# GeekIMUv1_Reciver.net
KiCad netlist of a schematic drawn in Altium Designer
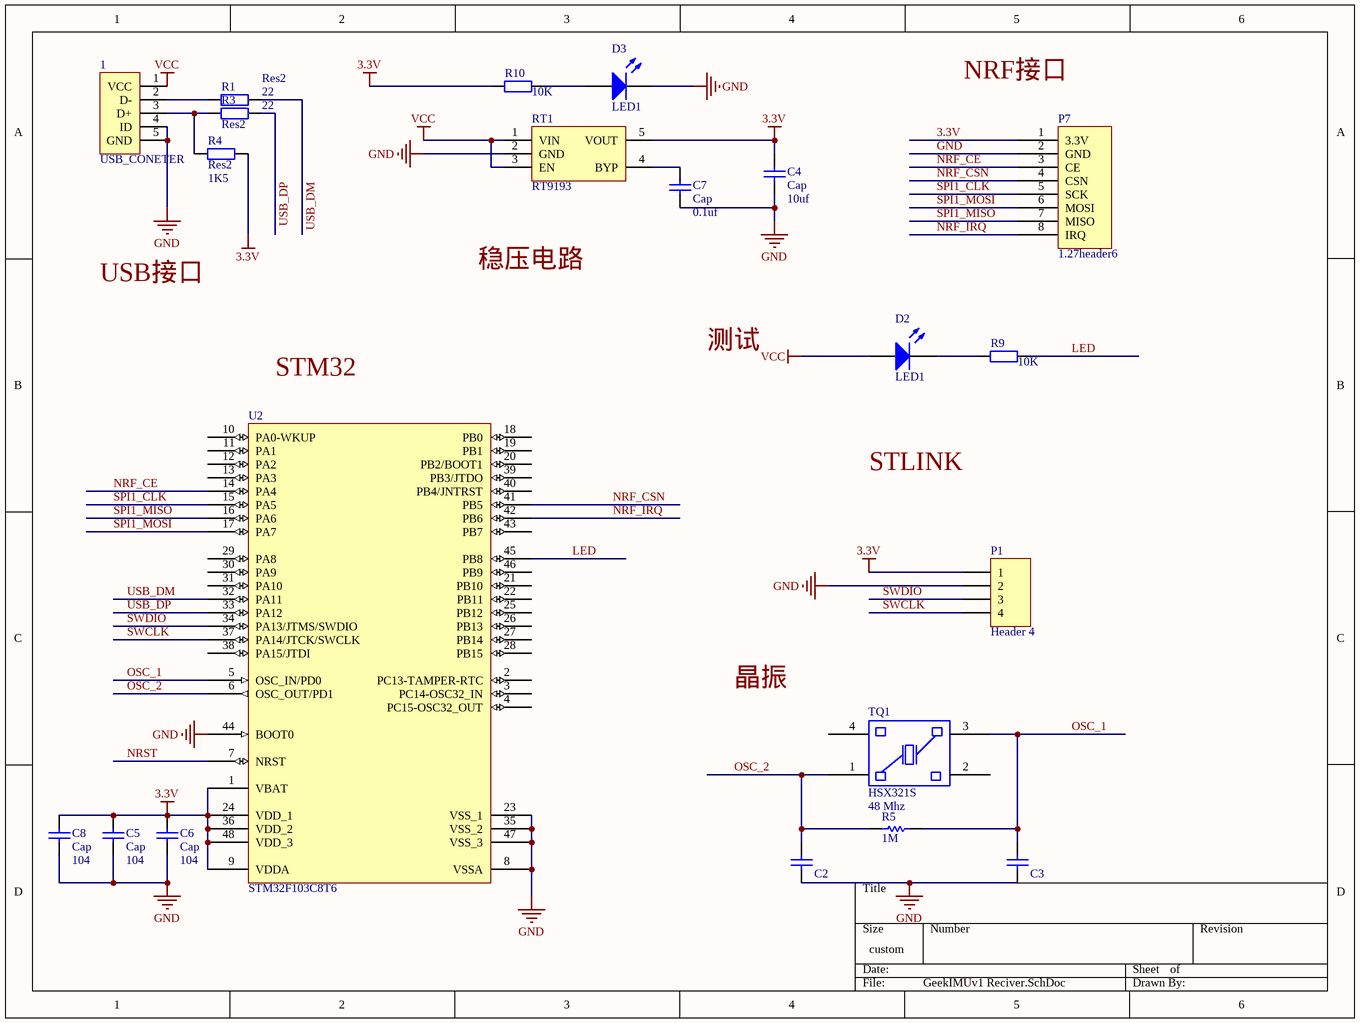
[diagram p0: GeekIMUv1 Reciver.SchDoc]

(export (version "E")
  (design (tool "Eeschema 10.0.6"))
  (components
    (comp (ref "1")
      (value "USB_CONETER")
      (footprint "USB A Plug")
      (description "USB")
      (fields (field (name "PUBLISHER") "Altium Limited"))
      (libsource (lib "my1012") (part "USB_conect_B"))
    )
    (comp (ref "C2") (value "Cap") (footprint "C0402") (libsource (lib "refLib") (part "Cap")))
    (comp (ref "C3") (value "Cap") (footprint "C0402") (libsource (lib "refLib") (part "Cap")))
    (comp (ref "C4")
      (value "Cap")
      (footprint "C0603")
      (description "Capacitor")
      (fields (field (name "ALTIUM_VALUE") "10uf") (field (name "PUBLISHER") "Altium Limited"))
      (libsource (lib "Miscellaneous Devices") (part "Cap"))
    )
    (comp (ref "C5")
      (value "Cap")
      (footprint "C0402")
      (description "Capacitor")
      (fields (field (name "ALTIUM_VALUE") "104") (field (name "PUBLISHER") "Altium Limited"))
      (libsource (lib "my1012") (part "Cap"))
    )
    (comp (ref "C6")
      (value "Cap")
      (footprint "C0402")
      (description "Capacitor")
      (fields (field (name "ALTIUM_VALUE") "104") (field (name "PUBLISHER") "Altium Limited"))
      (libsource (lib "my1012") (part "Cap"))
    )
    (comp (ref "C7")
      (value "Cap")
      (footprint "B0402")
      (description "Capacitor")
      (fields (field (name "ALTIUM_VALUE") "0.1uf") (field (name "PUBLISHER") "Altium Limited"))
      (libsource (lib "Miscellaneous Devices") (part "Cap"))
    )
    (comp (ref "C8")
      (value "Cap")
      (footprint "C0402")
      (description "Capacitor")
      (fields (field (name "ALTIUM_VALUE") "104") (field (name "PUBLISHER") "Altium Limited"))
      (libsource (lib "my1012") (part "Cap"))
    )
    (comp (ref "D2")
      (value "LED1")
      (footprint "C0402")
      (description "Typical RED GaAs LED")
      (fields (field (name "PUBLISHER") "Altium Limited"))
      (libsource (lib "my1012") (part "LED1"))
    )
    (comp (ref "D3")
      (value "LED1")
      (footprint "C0402")
      (description "Typical RED GaAs LED")
      (fields (field (name "PUBLISHER") "Altium Limited"))
      (libsource (lib "my1012") (part "LED1"))
    )
    (comp (ref "P1")
      (value "Header 4")
      (footprint "HDR1X4")
      (description "Header, 4-Pin")
      (fields (field (name "PUBLISHER") "Altium Limited"))
      (libsource (lib "Miscellaneous Connectors") (part "Header 4"))
    )
    (comp (ref "P7")
      (value "1.27header6")
      (footprint "1.27header6")
      (libsource (lib "1.27header6") (part "1.27header6"))
    )
    (comp (ref "R1")
      (value "Res2")
      (footprint "B0402")
      (description "Resistor")
      (fields (field (name "ALTIUM_VALUE") "22") (field (name "PUBLISHER") "Altium Limited"))
      (libsource (lib "my1012") (part "Res2"))
    )
    (comp (ref "R3")
      (value "Res2")
      (footprint "B0402")
      (description "Resistor")
      (fields (field (name "ALTIUM_VALUE") "22") (field (name "PUBLISHER") "Altium Limited"))
      (libsource (lib "my1012") (part "Res2"))
    )
    (comp (ref "R4")
      (value "Res2")
      (footprint "B0402")
      (description "Resistor")
      (fields (field (name "ALTIUM_VALUE") "1K5") (field (name "PUBLISHER") "Altium Limited"))
      (libsource (lib "my1012") (part "Res2"))
    )
    (comp (ref "R5")
      (value "1M")
      (footprint "R0402")
      (description "Semiconductor Resistor")
      (fields (field (name "Comment") "Res Semi"))
      (libsource (lib "refLib") (part "Res Semi"))
    )
    (comp (ref "R9")
      (value "10K")
      (footprint "B0402")
      (description "Resistor")
      (fields (field (name "PUBLISHER") "Altium Limited"))
      (libsource (lib "") (part "Res2_1"))
    )
    (comp (ref "R10")
      (value "10K")
      (footprint "B0402")
      (description "Resistor")
      (fields (field (name "PUBLISHER") "Altium Limited"))
      (libsource (lib "") (part "Res2_1"))
    )
    (comp (ref "RT1")
      (value "RT9193")
      (footprint "SOT23-5")
      (description "Power")
      (libsource (lib "SmartIMU") (part "RT9193"))
    )
    (comp (ref "TQ1")
      (value "HSX321S")
      (footprint "DSX321G")
      (description "XTAL")
      (fields (field (name "ALTIUM_VALUE") "48 Mhz"))
      (libsource (lib "refLib") (part "HSX321S"))
    )
    (comp (ref "U2")
      (value "STM32F103C8T6")
      (footprint "LQFP48")
      (description "STM32 ARM-based 32-bit MCU with 64 Kbytes Flash, 48-pin LQFP, Industrial Temperature")
      (fields (field (name "PUBLISHER") "Altium Limited"))
      (libsource (lib "ST Microcontroller 32-Bit STM32") (part "STM32F103C8T6"))
    )
  )
  (nets
    (net (code "1") (name "/LED") (class "Default")
      (node (ref "R9") (pin "1") (pinfunction "1_1") (pintype "passive"))
      (node (ref "U2") (pin "45") (pinfunction "PB8_45") (pintype "bidirectional"))
    )
    (net (code "2") (name "/NRF_CE") (class "Default")
      (node (ref "P7") (pin "3") (pinfunction "CE_3") (pintype "passive"))
      (node (ref "U2") (pin "14") (pinfunction "PA4_14") (pintype "bidirectional"))
    )
    (net (code "3") (name "/NRF_CSN") (class "Default")
      (node (ref "P7") (pin "4") (pinfunction "CSN_4") (pintype "passive"))
      (node (ref "U2") (pin "41") (pinfunction "PB5_41") (pintype "bidirectional"))
    )
    (net (code "4") (name "/NRF_IRQ") (class "Default")
      (node (ref "P7") (pin "8") (pinfunction "IRQ_8") (pintype "passive"))
      (node (ref "U2") (pin "42") (pinfunction "PB6_42") (pintype "bidirectional"))
    )
    (net (code "6") (name "/NRST") (class "Default")
      (node (ref "U2") (pin "7") (pinfunction "NRST_7") (pintype "bidirectional"))
    )
    (net (code "7") (name "/OSC_1") (class "Default")
      (node (ref "C3") (pin "2") (pinfunction "2_2") (pintype "passive"))
      (node (ref "R5") (pin "2") (pinfunction "2_2") (pintype "passive"))
      (node (ref "TQ1") (pin "3") (pinfunction "3_3") (pintype "passive"))
      (node (ref "U2") (pin "5") (pinfunction "OSC_IN/PD0_5") (pintype "input"))
    )
    (net (code "8") (name "/OSC_2") (class "Default")
      (node (ref "C2") (pin "2") (pinfunction "2_2") (pintype "passive"))
      (node (ref "R5") (pin "1") (pinfunction "1_1") (pintype "passive"))
      (node (ref "TQ1") (pin "1") (pinfunction "1_1") (pintype "passive"))
      (node (ref "U2") (pin "6") (pinfunction "OSC_OUT/PD1_6") (pintype "output"))
    )
    (net (code "9") (name "/SPI1_CLK") (class "Default")
      (node (ref "P7") (pin "5") (pinfunction "SCK_5") (pintype "passive"))
      (node (ref "U2") (pin "15") (pinfunction "PA5_15") (pintype "bidirectional"))
    )
    (net (code "10") (name "/SPI1_MISO") (class "Default")
      (node (ref "P7") (pin "7") (pinfunction "MISO_7") (pintype "passive"))
      (node (ref "U2") (pin "16") (pinfunction "PA6_16") (pintype "bidirectional"))
    )
    (net (code "11") (name "/SPI1_MOSI") (class "Default")
      (node (ref "P7") (pin "6") (pinfunction "MOSI_6") (pintype "passive"))
      (node (ref "U2") (pin "17") (pinfunction "PA7_17") (pintype "bidirectional"))
    )
    (net (code "14") (name "/SWCLK") (class "Default")
      (node (ref "P1") (pin "4") (pinfunction "4_4") (pintype "passive"))
      (node (ref "U2") (pin "37") (pinfunction "PA14/JTCK/SWCLK_37") (pintype "bidirectional"))
    )
    (net (code "15") (name "/SWDIO") (class "Default")
      (node (ref "P1") (pin "3") (pinfunction "3_3") (pintype "passive"))
      (node (ref "U2") (pin "34") (pinfunction "PA13/JTMS/SWDIO_34") (pintype "bidirectional"))
    )
    (net (code "16") (name "/USB_DM") (class "Default")
      (node (ref "R1") (pin "2") (pinfunction "2_2") (pintype "passive"))
      (node (ref "U2") (pin "32") (pinfunction "PA11_32") (pintype "bidirectional"))
    )
    (net (code "17") (name "/USB_DP") (class "Default")
      (node (ref "R3") (pin "2") (pinfunction "2_2") (pintype "passive"))
      (node (ref "U2") (pin "33") (pinfunction "PA12_33") (pintype "bidirectional"))
    )
    (net (code "22") (name "3.3V") (class "Default")
      (node (ref "C4") (pin "2") (pinfunction "2_2") (pintype "passive"))
      (node (ref "C5") (pin "2") (pinfunction "2_2") (pintype "passive"))
      (node (ref "C6") (pin "2") (pinfunction "2_2") (pintype "passive"))
      (node (ref "C8") (pin "2") (pinfunction "2_2") (pintype "passive"))
      (node (ref "P1") (pin "1") (pinfunction "1_1") (pintype "passive"))
      (node (ref "P7") (pin "1") (pinfunction "3.3V_1") (pintype "passive"))
      (node (ref "R10") (pin "2") (pinfunction "2_2") (pintype "passive"))
      (node (ref "R4") (pin "2") (pinfunction "2_2") (pintype "passive"))
      (node (ref "RT1") (pin "5") (pinfunction "VOUT_5") (pintype "passive"))
      (node (ref "U2") (pin "1") (pinfunction "VBAT_1") (pintype "power_in"))
      (node (ref "U2") (pin "24") (pinfunction "VDD_1_24") (pintype "power_in"))
      (node (ref "U2") (pin "36") (pinfunction "VDD_2_36") (pintype "power_in"))
      (node (ref "U2") (pin "48") (pinfunction "VDD_3_48") (pintype "power_in"))
      (node (ref "U2") (pin "9") (pinfunction "VDDA_9") (pintype "power_in"))
    )
    (net (code "23") (name "GND") (class "Default")
      (node (ref "1") (pin "4") (pinfunction "ID_4") (pintype "passive"))
      (node (ref "1") (pin "5") (pinfunction "GND_5") (pintype "passive"))
      (node (ref "C2") (pin "1") (pinfunction "1_1") (pintype "passive"))
      (node (ref "C3") (pin "1") (pinfunction "1_1") (pintype "passive"))
      (node (ref "C4") (pin "1") (pinfunction "1_1") (pintype "passive"))
      (node (ref "C5") (pin "1") (pinfunction "1_1") (pintype "passive"))
      (node (ref "C6") (pin "1") (pinfunction "1_1") (pintype "passive"))
      (node (ref "C7") (pin "1") (pinfunction "1_1") (pintype "passive"))
      (node (ref "C8") (pin "1") (pinfunction "1_1") (pintype "passive"))
      (node (ref "D3") (pin "2") (pinfunction "K_2") (pintype "passive"))
      (node (ref "P1") (pin "2") (pinfunction "2_2") (pintype "passive"))
      (node (ref "P7") (pin "2") (pinfunction "GND_2") (pintype "passive"))
      (node (ref "RT1") (pin "2") (pinfunction "GND_2") (pintype "passive"))
      (node (ref "U2") (pin "23") (pinfunction "VSS_1_23") (pintype "power_in"))
      (node (ref "U2") (pin "35") (pinfunction "VSS_2_35") (pintype "power_in"))
      (node (ref "U2") (pin "44") (pinfunction "BOOT0_44") (pintype "input"))
      (node (ref "U2") (pin "47") (pinfunction "VSS_3_47") (pintype "power_in"))
      (node (ref "U2") (pin "8") (pinfunction "VSSA_8") (pintype "power_in"))
    )
    (net (code "24") (name "Net-(1-D+)") (class "Default")
      (node (ref "1") (pin "3") (pinfunction "D+_3") (pintype "passive"))
      (node (ref "R3") (pin "1") (pinfunction "1_1") (pintype "passive"))
      (node (ref "R4") (pin "1") (pinfunction "1_1") (pintype "passive"))
    )
    (net (code "25") (name "Net-(1-D-)") (class "Default")
      (node (ref "1") (pin "2") (pinfunction "D-_2") (pintype "passive"))
      (node (ref "R1") (pin "1") (pinfunction "1_1") (pintype "passive"))
    )
    (net (code "26") (name "Net-(D2-K)") (class "Default")
      (node (ref "D2") (pin "2") (pinfunction "K_2") (pintype "passive"))
      (node (ref "R9") (pin "2") (pinfunction "2_2") (pintype "passive"))
    )
    (net (code "27") (name "Net-(D3-A)") (class "Default")
      (node (ref "D3") (pin "1") (pinfunction "A_1") (pintype "passive"))
      (node (ref "R10") (pin "1") (pinfunction "1_1") (pintype "passive"))
    )
    (net (code "28") (name "Net-(RT1-BYP)") (class "Default")
      (node (ref "C7") (pin "2") (pinfunction "2_2") (pintype "passive"))
      (node (ref "RT1") (pin "4") (pinfunction "BYP_4") (pintype "passive"))
    )
    (net (code "29") (name "VCC") (class "Default")
      (node (ref "1") (pin "1") (pinfunction "VCC_1") (pintype "passive"))
      (node (ref "D2") (pin "1") (pinfunction "A_1") (pintype "passive"))
      (node (ref "RT1") (pin "1") (pinfunction "VIN_1") (pintype "passive"))
      (node (ref "RT1") (pin "3") (pinfunction "EN_3") (pintype "power_in"))
    )
    (net (code "30") (name "unconnected-(TQ1-Pad2)") (class "Default")
      (node (ref "TQ1") (pin "2") (pinfunction "2_2") (pintype "passive"))
    )
    (net (code "31") (name "unconnected-(TQ1-Pad4)") (class "Default")
      (node (ref "TQ1") (pin "4") (pinfunction "4_4") (pintype "passive"))
    )
    (net (code "32") (name "unconnected-(U2-PA0-WKUP-Pad10)") (class "Default")
      (node (ref "U2") (pin "10") (pinfunction "PA0-WKUP_10") (pintype "bidirectional"))
    )
    (net (code "33") (name "unconnected-(U2-PA1-Pad11)") (class "Default")
      (node (ref "U2") (pin "11") (pinfunction "PA1_11") (pintype "bidirectional"))
    )
    (net (code "34") (name "unconnected-(U2-PA2-Pad12)") (class "Default")
      (node (ref "U2") (pin "12") (pinfunction "PA2_12") (pintype "bidirectional"))
    )
    (net (code "35") (name "unconnected-(U2-PA3-Pad13)") (class "Default")
      (node (ref "U2") (pin "13") (pinfunction "PA3_13") (pintype "bidirectional"))
    )
    (net (code "36") (name "unconnected-(U2-PA8-Pad29)") (class "Default")
      (node (ref "U2") (pin "29") (pinfunction "PA8_29") (pintype "bidirectional"))
    )
    (net (code "37") (name "unconnected-(U2-PA9-Pad30)") (class "Default")
      (node (ref "U2") (pin "30") (pinfunction "PA9_30") (pintype "bidirectional"))
    )
    (net (code "38") (name "unconnected-(U2-PA10-Pad31)") (class "Default")
      (node (ref "U2") (pin "31") (pinfunction "PA10_31") (pintype "bidirectional"))
    )
    (net (code "39") (name "unconnected-(U2-PA15{slash}JTDI-Pad38)") (class "Default")
      (node (ref "U2") (pin "38") (pinfunction "PA15/JTDI_38") (pintype "bidirectional"))
    )
    (net (code "40") (name "unconnected-(U2-PB0-Pad18)") (class "Default")
      (node (ref "U2") (pin "18") (pinfunction "PB0_18") (pintype "bidirectional"))
    )
    (net (code "41") (name "unconnected-(U2-PB1-Pad19)") (class "Default")
      (node (ref "U2") (pin "19") (pinfunction "PB1_19") (pintype "bidirectional"))
    )
    (net (code "42") (name "unconnected-(U2-PB2{slash}BOOT1-Pad20)") (class "Default")
      (node (ref "U2") (pin "20") (pinfunction "PB2/BOOT1_20") (pintype "bidirectional"))
    )
    (net (code "43") (name "unconnected-(U2-PB3{slash}JTDO-Pad39)") (class "Default")
      (node (ref "U2") (pin "39") (pinfunction "PB3/JTDO_39") (pintype "bidirectional"))
    )
    (net (code "44") (name "unconnected-(U2-PB4{slash}JNTRST-Pad40)") (class "Default")
      (node (ref "U2") (pin "40") (pinfunction "PB4/JNTRST_40") (pintype "bidirectional"))
    )
    (net (code "45") (name "unconnected-(U2-PB7-Pad43)") (class "Default")
      (node (ref "U2") (pin "43") (pinfunction "PB7_43") (pintype "bidirectional"))
    )
    (net (code "46") (name "unconnected-(U2-PB9-Pad46)") (class "Default")
      (node (ref "U2") (pin "46") (pinfunction "PB9_46") (pintype "bidirectional"))
    )
    (net (code "47") (name "unconnected-(U2-PB10-Pad21)") (class "Default")
      (node (ref "U2") (pin "21") (pinfunction "PB10_21") (pintype "bidirectional"))
    )
    (net (code "48") (name "unconnected-(U2-PB11-Pad22)") (class "Default")
      (node (ref "U2") (pin "22") (pinfunction "PB11_22") (pintype "bidirectional"))
    )
    (net (code "49") (name "unconnected-(U2-PB12-Pad25)") (class "Default")
      (node (ref "U2") (pin "25") (pinfunction "PB12_25") (pintype "bidirectional"))
    )
    (net (code "50") (name "unconnected-(U2-PB13-Pad26)") (class "Default")
      (node (ref "U2") (pin "26") (pinfunction "PB13_26") (pintype "bidirectional"))
    )
    (net (code "51") (name "unconnected-(U2-PB14-Pad27)") (class "Default")
      (node (ref "U2") (pin "27") (pinfunction "PB14_27") (pintype "bidirectional"))
    )
    (net (code "52") (name "unconnected-(U2-PB15-Pad28)") (class "Default")
      (node (ref "U2") (pin "28") (pinfunction "PB15_28") (pintype "bidirectional"))
    )
    (net (code "53") (name "unconnected-(U2-PC13-TAMPER-RTC-Pad2)") (class "Default")
      (node (ref "U2") (pin "2") (pinfunction "PC13-TAMPER-RTC_2") (pintype "bidirectional"))
    )
    (net (code "54") (name "unconnected-(U2-PC14-OSC32_IN-Pad3)") (class "Default")
      (node (ref "U2") (pin "3") (pinfunction "PC14-OSC32_IN_3") (pintype "bidirectional"))
    )
    (net (code "55") (name "unconnected-(U2-PC15-OSC32_OUT-Pad4)") (class "Default")
      (node (ref "U2") (pin "4") (pinfunction "PC15-OSC32_OUT_4") (pintype "bidirectional"))
    )
  )
)
